# logic.net
KiCad netlist of a schematic drawn in EAGLE
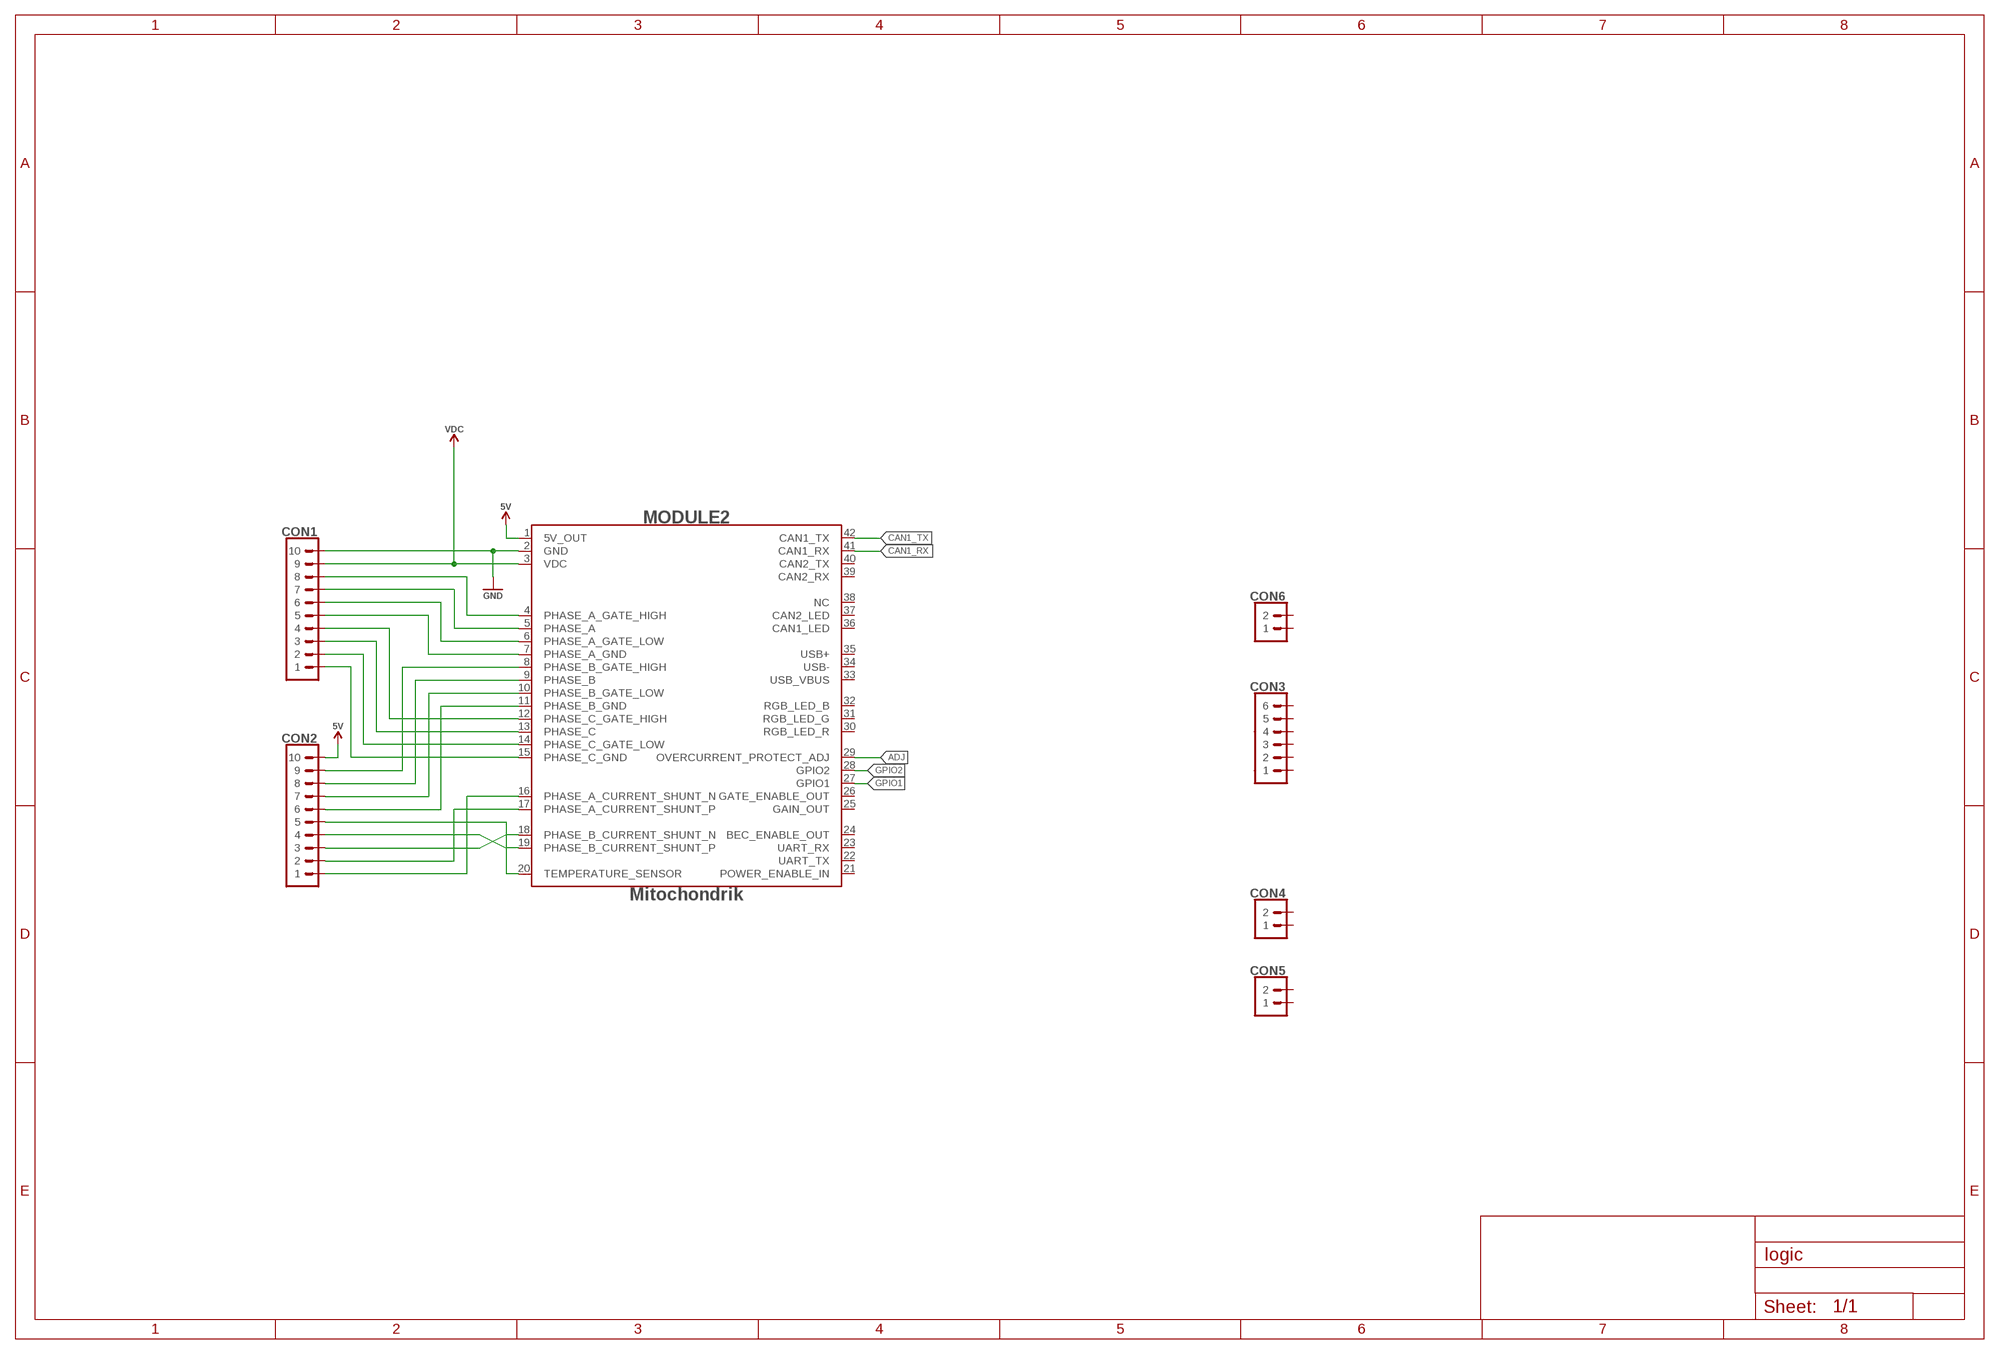
[diagram p0: schematic, sheet 1]

(export (version "E")
  (design (tool "Eeschema 10.0.6"))
  (components
    (comp (ref "CON1")
      (value "PINHEAD_1X10-2")
      (footprint "eagle-import:1X10-PTH_2")
      (libsource (lib "eagle-import") (part "PINHEAD_1X10-2"))
    )
    (comp (ref "CON2")
      (value "PINHEAD_1X10-2")
      (footprint "eagle-import:1X10-PTH_2")
      (libsource (lib "eagle-import") (part "PINHEAD_1X10-2"))
    )
    (comp (ref "CON3")
      (value "PINHEAD_1X06-2")
      (footprint "eagle-import:1X06-PTH-2")
      (libsource (lib "eagle-import") (part "PINHEAD_1X06-2"))
    )
    (comp (ref "CON4")
      (value "PINHEAD_1X02-2")
      (footprint "eagle-import:1X02-PTH-2")
      (libsource (lib "eagle-import") (part "PINHEAD_1X02-2"))
    )
    (comp (ref "CON5")
      (value "PINHEAD_1X02-2")
      (footprint "eagle-import:1X02-PTH-2")
      (libsource (lib "eagle-import") (part "PINHEAD_1X02-2"))
    )
    (comp (ref "CON6")
      (value "PINHEAD_1X02-2")
      (footprint "eagle-import:1X02-PTH-2")
      (libsource (lib "eagle-import") (part "PINHEAD_1X02-2"))
    )
    (comp (ref "MODULE2")
      (value "MITOHONDRIQUE-TH")
      (footprint "eagle-import:MITOHONDRIQUE")
      (fields (field (name "MANF#") "Mitochondrik") (field (name "MANF") "Zubax Robotics"))
      (libsource (lib "eagle-import") (part "MITOHONDRIQUE-TH"))
    )
  )
  (nets
    (net (code "1") (name "5V") (class "Default")
      (node (ref "CON2") (pin "10") (pinfunction "10_10") (pintype "passive"))
      (node (ref "MODULE2") (pin "1") (pinfunction "5V_OUT_1") (pintype "power_in"))
    )
    (net (code "2") (name "ADJ") (class "Default")
      (node (ref "MODULE2") (pin "29") (pinfunction "OVERCURRENT_PROTECT_ADJ_29") (pintype "input"))
    )
    (net (code "3") (name "CAN1_RX") (class "Default")
      (node (ref "MODULE2") (pin "41") (pinfunction "CAN1_RX_41") (pintype "input"))
    )
    (net (code "4") (name "CAN1_TX") (class "Default")
      (node (ref "MODULE2") (pin "42") (pinfunction "CAN1_TX_42") (pintype "output"))
    )
    (net (code "5") (name "GND") (class "Default")
      (node (ref "CON1") (pin "10") (pinfunction "10_10") (pintype "passive"))
      (node (ref "MODULE2") (pin "2") (pinfunction "GND_2") (pintype "power_in"))
    )
    (net (code "6") (name "GPIO1") (class "Default")
      (node (ref "MODULE2") (pin "27") (pinfunction "GPIO1_27") (pintype "bidirectional"))
    )
    (net (code "7") (name "GPIO2") (class "Default")
      (node (ref "MODULE2") (pin "28") (pinfunction "GPIO2_28") (pintype "bidirectional"))
    )
    (net (code "8") (name "Net-(MODULE2-PHASE_A)") (class "Default")
      (node (ref "CON1") (pin "7") (pinfunction "7_7") (pintype "passive"))
      (node (ref "MODULE2") (pin "5") (pinfunction "PHASE_A_5") (pintype "input"))
    )
    (net (code "9") (name "Net-(MODULE2-PHASE_A_CURRENT_SHUNT_N)") (class "Default")
      (node (ref "CON2") (pin "1") (pinfunction "1_1") (pintype "passive"))
      (node (ref "MODULE2") (pin "16") (pinfunction "PHASE_A_CURRENT_SHUNT_N_16") (pintype "input"))
    )
    (net (code "10") (name "Net-(MODULE2-PHASE_A_CURRENT_SHUNT_P)") (class "Default")
      (node (ref "CON2") (pin "2") (pinfunction "2_2") (pintype "passive"))
      (node (ref "MODULE2") (pin "17") (pinfunction "PHASE_A_CURRENT_SHUNT_P_17") (pintype "input"))
    )
    (net (code "11") (name "Net-(MODULE2-PHASE_A_GATE_HIGH)") (class "Default")
      (node (ref "CON1") (pin "8") (pinfunction "8_8") (pintype "passive"))
      (node (ref "MODULE2") (pin "4") (pinfunction "PHASE_A_GATE_HIGH_4") (pintype "output"))
    )
    (net (code "12") (name "Net-(MODULE2-PHASE_A_GATE_LOW)") (class "Default")
      (node (ref "CON1") (pin "6") (pinfunction "6_6") (pintype "passive"))
      (node (ref "MODULE2") (pin "6") (pinfunction "PHASE_A_GATE_LOW_6") (pintype "output"))
    )
    (net (code "13") (name "Net-(MODULE2-PHASE_A_GND)") (class "Default")
      (node (ref "CON1") (pin "5") (pinfunction "5_5") (pintype "passive"))
      (node (ref "MODULE2") (pin "7") (pinfunction "PHASE_A_GND_7") (pintype "input"))
    )
    (net (code "14") (name "Net-(MODULE2-PHASE_B)") (class "Default")
      (node (ref "CON2") (pin "8") (pinfunction "8_8") (pintype "passive"))
      (node (ref "MODULE2") (pin "9") (pinfunction "PHASE_B_9") (pintype "input"))
    )
    (net (code "15") (name "Net-(MODULE2-PHASE_B_CURRENT_SHUNT_N)") (class "Default")
      (node (ref "CON2") (pin "3") (pinfunction "3_3") (pintype "passive"))
      (node (ref "MODULE2") (pin "18") (pinfunction "PHASE_B_CURRENT_SHUNT_N_18") (pintype "input"))
    )
    (net (code "16") (name "Net-(MODULE2-PHASE_B_CURRENT_SHUNT_P)") (class "Default")
      (node (ref "CON2") (pin "4") (pinfunction "4_4") (pintype "passive"))
      (node (ref "MODULE2") (pin "19") (pinfunction "PHASE_B_CURRENT_SHUNT_P_19") (pintype "input"))
    )
    (net (code "17") (name "Net-(MODULE2-PHASE_B_GATE_HIGH)") (class "Default")
      (node (ref "CON2") (pin "9") (pinfunction "9_9") (pintype "passive"))
      (node (ref "MODULE2") (pin "8") (pinfunction "PHASE_B_GATE_HIGH_8") (pintype "output"))
    )
    (net (code "18") (name "Net-(MODULE2-PHASE_B_GATE_LOW)") (class "Default")
      (node (ref "CON2") (pin "7") (pinfunction "7_7") (pintype "passive"))
      (node (ref "MODULE2") (pin "10") (pinfunction "PHASE_B_GATE_LOW_10") (pintype "output"))
    )
    (net (code "19") (name "Net-(MODULE2-PHASE_B_GND)") (class "Default")
      (node (ref "CON2") (pin "6") (pinfunction "6_6") (pintype "passive"))
      (node (ref "MODULE2") (pin "11") (pinfunction "PHASE_B_GND_11") (pintype "input"))
    )
    (net (code "20") (name "Net-(MODULE2-PHASE_C)") (class "Default")
      (node (ref "CON1") (pin "3") (pinfunction "3_3") (pintype "passive"))
      (node (ref "MODULE2") (pin "13") (pinfunction "PHASE_C_13") (pintype "input"))
    )
    (net (code "21") (name "Net-(MODULE2-PHASE_C_GATE_HIGH)") (class "Default")
      (node (ref "CON1") (pin "4") (pinfunction "4_4") (pintype "passive"))
      (node (ref "MODULE2") (pin "12") (pinfunction "PHASE_C_GATE_HIGH_12") (pintype "output"))
    )
    (net (code "22") (name "Net-(MODULE2-PHASE_C_GATE_LOW)") (class "Default")
      (node (ref "CON1") (pin "2") (pinfunction "2_2") (pintype "passive"))
      (node (ref "MODULE2") (pin "14") (pinfunction "PHASE_C_GATE_LOW_14") (pintype "output"))
    )
    (net (code "23") (name "Net-(MODULE2-PHASE_C_GND)") (class "Default")
      (node (ref "CON1") (pin "1") (pinfunction "1_1") (pintype "passive"))
      (node (ref "MODULE2") (pin "15") (pinfunction "PHASE_C_GND_15") (pintype "input"))
    )
    (net (code "24") (name "Net-(MODULE2-TEMPERATURE_SENSOR)") (class "Default")
      (node (ref "CON2") (pin "5") (pinfunction "5_5") (pintype "passive"))
      (node (ref "MODULE2") (pin "20") (pinfunction "TEMPERATURE_SENSOR_20") (pintype "input"))
    )
    (net (code "25") (name "VDC") (class "Default")
      (node (ref "CON1") (pin "9") (pinfunction "9_9") (pintype "passive"))
      (node (ref "MODULE2") (pin "3") (pinfunction "VDC_3") (pintype "power_in"))
    )
    (net (code "26") (name "unconnected-(CON3-Pad1)") (class "Default")
      (node (ref "CON3") (pin "1") (pinfunction "1_1") (pintype "passive"))
    )
    (net (code "27") (name "unconnected-(CON3-Pad2)") (class "Default")
      (node (ref "CON3") (pin "2") (pinfunction "2_2") (pintype "passive"))
    )
    (net (code "28") (name "unconnected-(CON3-Pad3)") (class "Default")
      (node (ref "CON3") (pin "3") (pinfunction "3_3") (pintype "passive"))
    )
    (net (code "29") (name "unconnected-(CON3-Pad4)") (class "Default")
      (node (ref "CON3") (pin "4") (pinfunction "4_4") (pintype "passive"))
    )
    (net (code "30") (name "unconnected-(CON3-Pad5)") (class "Default")
      (node (ref "CON3") (pin "5") (pinfunction "5_5") (pintype "passive"))
    )
    (net (code "31") (name "unconnected-(CON3-Pad6)") (class "Default")
      (node (ref "CON3") (pin "6") (pinfunction "6_6") (pintype "passive"))
    )
    (net (code "32") (name "unconnected-(CON4-Pad1)") (class "Default")
      (node (ref "CON4") (pin "1") (pinfunction "1_1") (pintype "passive"))
    )
    (net (code "33") (name "unconnected-(CON4-Pad2)") (class "Default")
      (node (ref "CON4") (pin "2") (pinfunction "2_2") (pintype "passive"))
    )
    (net (code "34") (name "unconnected-(CON5-Pad1)") (class "Default")
      (node (ref "CON5") (pin "1") (pinfunction "1_1") (pintype "passive"))
    )
    (net (code "35") (name "unconnected-(CON5-Pad2)") (class "Default")
      (node (ref "CON5") (pin "2") (pinfunction "2_2") (pintype "passive"))
    )
    (net (code "36") (name "unconnected-(CON6-Pad1)") (class "Default")
      (node (ref "CON6") (pin "1") (pinfunction "1_1") (pintype "passive"))
    )
    (net (code "37") (name "unconnected-(CON6-Pad2)") (class "Default")
      (node (ref "CON6") (pin "2") (pinfunction "2_2") (pintype "passive"))
    )
    (net (code "38") (name "unconnected-(MODULE2-BEC_ENABLE_OUT-Pad24)") (class "Default")
      (node (ref "MODULE2") (pin "24") (pinfunction "BEC_ENABLE_OUT_24") (pintype "output"))
    )
    (net (code "39") (name "unconnected-(MODULE2-CAN1_LED-Pad36)") (class "Default")
      (node (ref "MODULE2") (pin "36") (pinfunction "CAN1_LED_36") (pintype "output"))
    )
    (net (code "40") (name "unconnected-(MODULE2-CAN2_LED-Pad37)") (class "Default")
      (node (ref "MODULE2") (pin "37") (pinfunction "CAN2_LED_37") (pintype "output"))
    )
    (net (code "41") (name "unconnected-(MODULE2-CAN2_RX-Pad39)") (class "Default")
      (node (ref "MODULE2") (pin "39") (pinfunction "CAN2_RX_39") (pintype "input"))
    )
    (net (code "42") (name "unconnected-(MODULE2-CAN2_TX-Pad40)") (class "Default")
      (node (ref "MODULE2") (pin "40") (pinfunction "CAN2_TX_40") (pintype "output"))
    )
    (net (code "43") (name "unconnected-(MODULE2-GAIN_OUT-Pad25)") (class "Default")
      (node (ref "MODULE2") (pin "25") (pinfunction "GAIN_OUT_25") (pintype "output"))
    )
    (net (code "44") (name "unconnected-(MODULE2-GATE_ENABLE_OUT-Pad26)") (class "Default")
      (node (ref "MODULE2") (pin "26") (pinfunction "GATE_ENABLE_OUT_26") (pintype "output"))
    )
    (net (code "45") (name "unconnected-(MODULE2-NC-Pad38)") (class "Default")
      (node (ref "MODULE2") (pin "38") (pinfunction "NC_38") (pintype "no_connect"))
    )
    (net (code "46") (name "unconnected-(MODULE2-POWER_ENABLE_IN-Pad21)") (class "Default")
      (node (ref "MODULE2") (pin "21") (pinfunction "POWER_ENABLE_IN_21") (pintype "input"))
    )
    (net (code "47") (name "unconnected-(MODULE2-RGB_LED_B-Pad32)") (class "Default")
      (node (ref "MODULE2") (pin "32") (pinfunction "RGB_LED_B_32") (pintype "output"))
    )
    (net (code "48") (name "unconnected-(MODULE2-RGB_LED_G-Pad31)") (class "Default")
      (node (ref "MODULE2") (pin "31") (pinfunction "RGB_LED_G_31") (pintype "output"))
    )
    (net (code "49") (name "unconnected-(MODULE2-RGB_LED_R-Pad30)") (class "Default")
      (node (ref "MODULE2") (pin "30") (pinfunction "RGB_LED_R_30") (pintype "output"))
    )
    (net (code "50") (name "unconnected-(MODULE2-UART_RX-Pad23)") (class "Default")
      (node (ref "MODULE2") (pin "23") (pinfunction "UART_RX_23") (pintype "input"))
    )
    (net (code "51") (name "unconnected-(MODULE2-UART_TX-Pad22)") (class "Default")
      (node (ref "MODULE2") (pin "22") (pinfunction "UART_TX_22") (pintype "output"))
    )
    (net (code "52") (name "unconnected-(MODULE2-USB+-Pad35)") (class "Default")
      (node (ref "MODULE2") (pin "35") (pinfunction "USB+_35") (pintype "bidirectional"))
    )
    (net (code "53") (name "unconnected-(MODULE2-USB--Pad34)") (class "Default")
      (node (ref "MODULE2") (pin "34") (pinfunction "USB-_34") (pintype "bidirectional"))
    )
    (net (code "54") (name "unconnected-(MODULE2-USB_VBUS-Pad33)") (class "Default")
      (node (ref "MODULE2") (pin "33") (pinfunction "USB_VBUS_33") (pintype "input"))
    )
  )
)
